# OutPut.net
KiCad netlist of a schematic drawn in Altium Designer
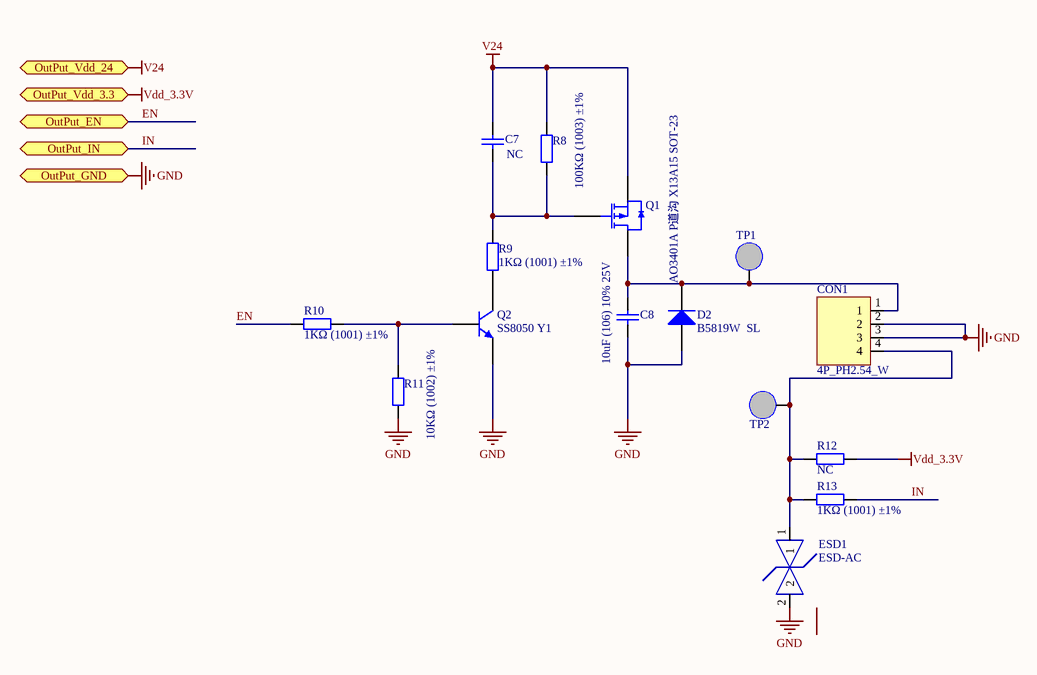
[diagram p0: OutPut.SchDoc]

(export (version "E")
  (design (tool "Eeschema 10.0.6"))
  (components
    (comp (ref "C7")
      (value "NC")
      (footprint "0805_C")
      (description "贴片电容")
      (libsource (lib "Miscellaneous Devices LC") (part "0805 22uF (226) 20% 25V"))
    )
    (comp (ref "C8")
      (value "10uF (106) 10% 25V")
      (footprint "0805_C")
      (description "贴片电容")
      (libsource (lib "Miscellaneous Devices LC") (part "0805 10uF (106) 10% 25V"))
    )
    (comp (ref "CON1")
      (value "4P_PH2.54_W")
      (footprint "PH2.0-WS-4P")
      (libsource (lib "mylib") (part "4P_XH2.54_W"))
    )
    (comp (ref "D2")
      (value "B5819W  SL")
      (footprint "SOD-123")
      (description "肖特基二极管")
      (libsource (lib "Miscellaneous Devices LC") (part "SOD-123 B5819W  SL"))
    )
    (comp (ref "ESD1") (value "ESD-AC") (footprint "SOD-523") (libsource (lib "mylib") (part "ESD-AC")))
    (comp (ref "Q1")
      (value "AO3401A P道沟 X13A15 SOT-23")
      (footprint "SOT-23-3L")
      (description "MOS(场效应管)")
      (libsource (lib "Miscellaneous Devices LC") (part "AO3401A P道沟 X13A15 SOT-23"))
    )
    (comp (ref "Q2")
      (value "SS8050 Y1")
      (footprint "SOT-23(SOT-23-3)")
      (description "三极管")
      (libsource (lib "Miscellaneous Devices LC") (part "SOT-23 SS8050 Y1"))
    )
    (comp (ref "R8")
      (value "100KΩ (1003) ±1%")
      (footprint "0805_R")
      (description "贴片电阻")
      (libsource (lib "Miscellaneous Devices LC") (part "0805 100KΩ (1003) 1%"))
    )
    (comp (ref "R9")
      (value "1KΩ (1001) ±1%")
      (footprint "0805_R")
      (description "贴片电阻")
      (libsource (lib "Miscellaneous Devices LC") (part "0805 1KΩ (1001) 1%"))
    )
    (comp (ref "R10")
      (value "1KΩ (1001) ±1%")
      (footprint "0805_R")
      (description "贴片电阻")
      (libsource (lib "") (part "0805 1KΩ (1001) 1%_1"))
    )
    (comp (ref "R11")
      (value "10KΩ (1002) ±1%")
      (footprint "0805_R")
      (description "贴片电阻")
      (libsource (lib "Miscellaneous Devices LC") (part "0805 10KΩ (1002) 1%"))
    )
    (comp (ref "R12")
      (value "NC")
      (footprint "0805_R")
      (description "贴片电阻")
      (libsource (lib "") (part "0805 1KΩ (1001) 1%_1"))
    )
    (comp (ref "R13")
      (value "1KΩ (1001) ±1%")
      (footprint "0805_R")
      (description "贴片电阻")
      (libsource (lib "") (part "0805 1KΩ (1001) 1%_1"))
    )
    (comp (ref "TP1") (value "TP") (footprint "TP") (libsource (lib "mylib") (part "TP")))
    (comp (ref "TP2") (value "TP") (footprint "TP") (libsource (lib "mylib") (part "TP")))
  )
  (nets
    (net (code "1") (name "/EN") (class "Default")
      (node (ref "R10") (pin "1") (pinfunction "1_1") (pintype "passive"))
    )
    (net (code "2") (name "/IN") (class "Default")
      (node (ref "R13") (pin "2") (pinfunction "2_2") (pintype "passive"))
    )
    (net (code "3") (name "GND") (class "Default")
      (node (ref "C8") (pin "1") (pinfunction "1_1") (pintype "passive"))
      (node (ref "CON1") (pin "2") (pinfunction "2_2") (pintype "passive"))
      (node (ref "CON1") (pin "3") (pinfunction "3_3") (pintype "passive"))
      (node (ref "D2") (pin "1") (pinfunction "A_1") (pintype "passive"))
      (node (ref "ESD1") (pin "2") (pinfunction "2_2") (pintype "passive"))
      (node (ref "Q2") (pin "2") (pinfunction "E_2") (pintype "passive"))
      (node (ref "R11") (pin "1") (pinfunction "1_1") (pintype "passive"))
    )
    (net (code "4") (name "Net-(CON1-Pad4)") (class "Default")
      (node (ref "CON1") (pin "4") (pinfunction "4_4") (pintype "passive"))
      (node (ref "ESD1") (pin "1") (pinfunction "1_1") (pintype "passive"))
      (node (ref "R12") (pin "1") (pinfunction "1_1") (pintype "passive"))
      (node (ref "R13") (pin "1") (pinfunction "1_1") (pintype "passive"))
      (node (ref "TP2") (pin "1") (pinfunction "1_1") (pintype "passive"))
    )
    (net (code "5") (name "Net-(D2-K)") (class "Default")
      (node (ref "C8") (pin "2") (pinfunction "2_2") (pintype "passive"))
      (node (ref "CON1") (pin "1") (pinfunction "1_1") (pintype "passive"))
      (node (ref "D2") (pin "2") (pinfunction "K_2") (pintype "passive"))
      (node (ref "Q1") (pin "3") (pinfunction "D_3") (pintype "passive"))
      (node (ref "TP1") (pin "1") (pinfunction "1_1") (pintype "passive"))
    )
    (net (code "6") (name "Net-(Q1-G)") (class "Default")
      (node (ref "C7") (pin "1") (pinfunction "1_1") (pintype "passive"))
      (node (ref "Q1") (pin "1") (pinfunction "G_1") (pintype "passive"))
      (node (ref "R8") (pin "1") (pinfunction "1_1") (pintype "passive"))
      (node (ref "R9") (pin "1") (pinfunction "1_1") (pintype "passive"))
    )
    (net (code "7") (name "Net-(Q2-B)") (class "Default")
      (node (ref "Q2") (pin "1") (pinfunction "B_1") (pintype "passive"))
      (node (ref "R10") (pin "2") (pinfunction "2_2") (pintype "passive"))
      (node (ref "R11") (pin "2") (pinfunction "2_2") (pintype "passive"))
    )
    (net (code "8") (name "Net-(Q2-C)") (class "Default")
      (node (ref "Q2") (pin "3") (pinfunction "C_3") (pintype "passive"))
      (node (ref "R9") (pin "2") (pinfunction "2_2") (pintype "passive"))
    )
    (net (code "9") (name "V24") (class "Default")
      (node (ref "C7") (pin "2") (pinfunction "2_2") (pintype "passive"))
      (node (ref "Q1") (pin "2") (pinfunction "S_2") (pintype "passive"))
      (node (ref "R8") (pin "2") (pinfunction "2_2") (pintype "passive"))
    )
    (net (code "10") (name "Vdd_3.3V") (class "Default")
      (node (ref "R12") (pin "2") (pinfunction "2_2") (pintype "passive"))
    )
    (net (code "11") (name "unconnected-(CON1-PadA)") (class "Default")
      (node (ref "CON1") (pin "A") (pinfunction "A_A") (pintype "passive"))
    )
    (net (code "12") (name "unconnected-(CON1-PadB)") (class "Default")
      (node (ref "CON1") (pin "B") (pinfunction "B_B") (pintype "passive"))
    )
  )
)
